# UPS-MAF-APU.net
KiCad netlist of a schematic drawn in EAGLE
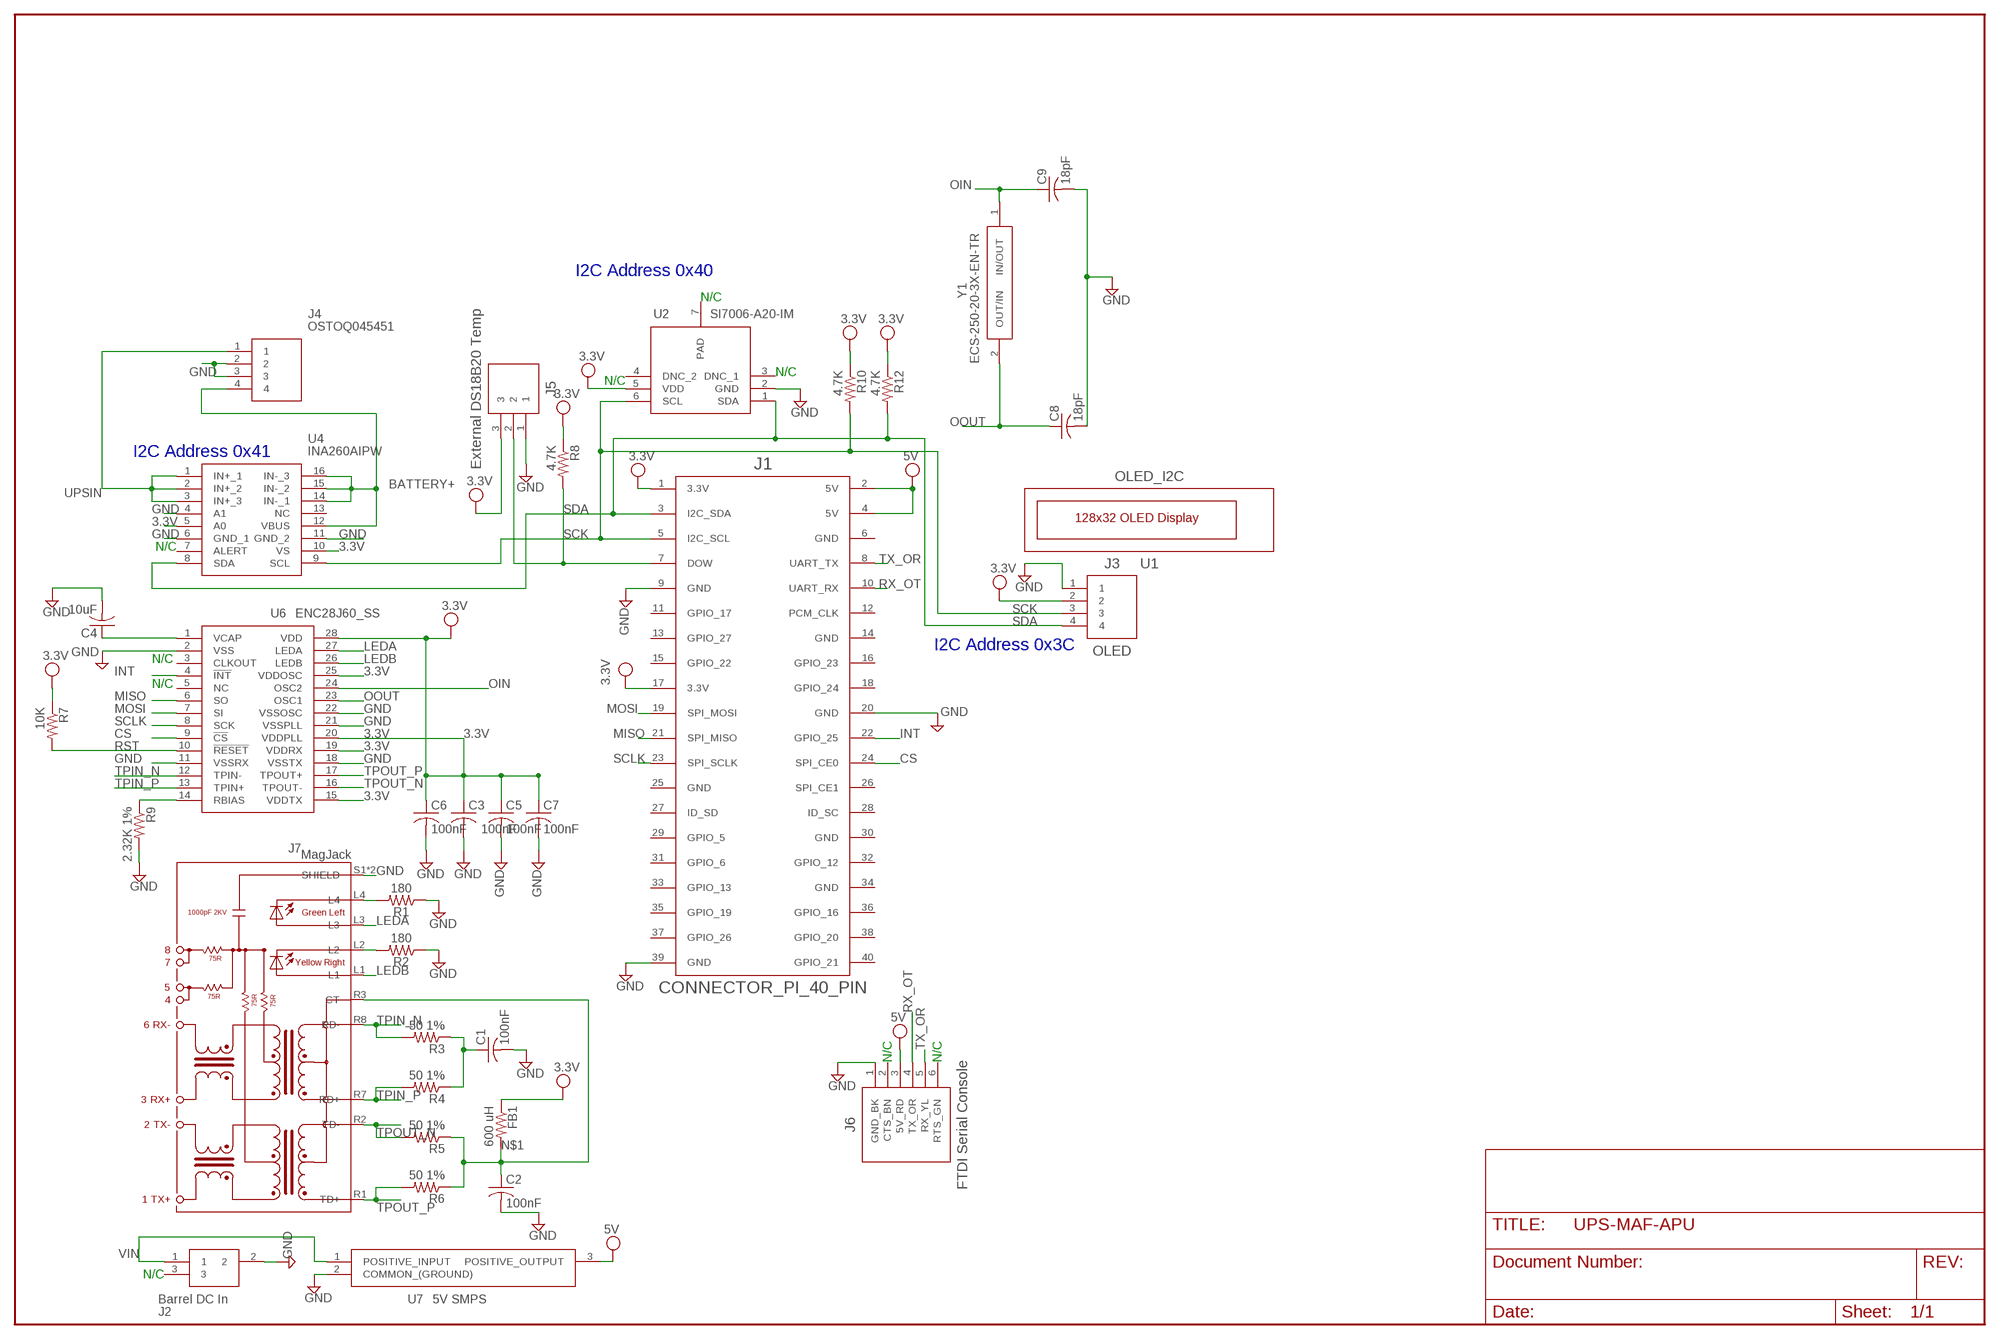
[diagram p0: schematic, sheet 1]

(export (version "E")
  (design (tool "Eeschema 10.0.6"))
  (components
    (comp (ref "C1")
      (value "100nF")
      (footprint "eagle-import:C0603")
      (libsource (lib "eagle-import") (part "C-USC0603"))
    )
    (comp (ref "C2")
      (value "100nF")
      (footprint "eagle-import:C0603")
      (libsource (lib "eagle-import") (part "C-USC0603"))
    )
    (comp (ref "C3")
      (value "100nF")
      (footprint "eagle-import:C0603")
      (libsource (lib "eagle-import") (part "C-USC0603"))
    )
    (comp (ref "C4")
      (value "10uF")
      (footprint "eagle-import:C0805")
      (libsource (lib "eagle-import") (part "C-USC0805"))
    )
    (comp (ref "C5")
      (value "100nF")
      (footprint "eagle-import:C0603")
      (libsource (lib "eagle-import") (part "C-USC0603"))
    )
    (comp (ref "C6")
      (value "100nF")
      (footprint "eagle-import:C0603")
      (libsource (lib "eagle-import") (part "C-USC0603"))
    )
    (comp (ref "C7")
      (value "100nF")
      (footprint "eagle-import:C0603")
      (libsource (lib "eagle-import") (part "C-USC0603"))
    )
    (comp (ref "C8")
      (value "18pF")
      (footprint "eagle-import:C0603")
      (libsource (lib "eagle-import") (part "C-USC0603"))
    )
    (comp (ref "C9")
      (value "18pF")
      (footprint "eagle-import:C0603")
      (libsource (lib "eagle-import") (part "C-USC0603"))
    )
    (comp (ref "FB1")
      (value "600 uH")
      (footprint "eagle-import:R0805")
      (libsource (lib "eagle-import") (part "R-US_R0805"))
    )
    (comp (ref "J1")
      (value "CONNECTOR_PI_40_PIN")
      (footprint "eagle-import:2X20")
      (libsource (lib "eagle-import") (part "CONNECTOR_PI_40_PIN"))
    )
    (comp (ref "J2")
      (value "Barrel DC In")
      (footprint "eagle-import:PJ-102AH")
      (fields
        (field (name "MANUFACTURER_PART_NUMBER") "PJ-102AH")
        (field (name "MOUSER_PART_NUMBER") "490-PJ-102AH")
      )
      (libsource (lib "eagle-import") (part "PJ-102AH"))
    )
    (comp (ref "J3")
      (value "OLED")
      (footprint "eagle-import:ESQ-104-XX-X-S")
      (libsource (lib "eagle-import") (part "CONNECTOR_4"))
    )
    (comp (ref "J4")
      (value "OSTOQ045451")
      (footprint "eagle-import:OSTOQ045451")
      (libsource (lib "eagle-import") (part "OSTOQ045451"))
    )
    (comp (ref "J5")
      (value "External DS18B20 Temp")
      (footprint "eagle-import:MOLEX_70553-0002")
      (libsource (lib "eagle-import") (part "CONNECTOR-3"))
    )
    (comp (ref "J6")
      (value "FTDI Serial Console")
      (footprint "eagle-import:ESQ-106-XX-X-S")
      (libsource (lib "eagle-import") (part "CONNECTOR-6-FTDI"))
    )
    (comp (ref "J7")
      (value "MagJack")
      (footprint "eagle-import:WIZNET_RB1-125BAG1A")
      (fields (field (name "MF") "WIZnet") (field (name "MP") "RB1-125BAG1A"))
      (libsource (lib "eagle-import") (part "RB1-125BAG1A"))
    )
    (comp (ref "R1")
      (value "180")
      (footprint "eagle-import:0603")
      (libsource (lib "eagle-import") (part "180OHM-0603-1/10W-1%"))
    )
    (comp (ref "R2")
      (value "180")
      (footprint "eagle-import:0603")
      (libsource (lib "eagle-import") (part "180OHM-0603-1/10W-1%"))
    )
    (comp (ref "R3")
      (value "50 1%")
      (footprint "eagle-import:R0805")
      (libsource (lib "eagle-import") (part "R-US_R0805"))
    )
    (comp (ref "R4")
      (value "50 1%")
      (footprint "eagle-import:R0805")
      (libsource (lib "eagle-import") (part "R-US_R0805"))
    )
    (comp (ref "R5")
      (value "50 1%")
      (footprint "eagle-import:R0805")
      (libsource (lib "eagle-import") (part "R-US_R0805"))
    )
    (comp (ref "R6")
      (value "50 1%")
      (footprint "eagle-import:R0805")
      (libsource (lib "eagle-import") (part "R-US_R0805"))
    )
    (comp (ref "R7")
      (value "10K")
      (footprint "eagle-import:R0805")
      (libsource (lib "eagle-import") (part "R-US_R0805"))
    )
    (comp (ref "R8")
      (value "4.7K")
      (footprint "eagle-import:R0805")
      (libsource (lib "eagle-import") (part "R-US_R0805"))
    )
    (comp (ref "R9")
      (value "2.32K 1%")
      (footprint "eagle-import:R0805")
      (libsource (lib "eagle-import") (part "R-US_R0805"))
    )
    (comp (ref "R10")
      (value "4.7K")
      (footprint "eagle-import:R0805")
      (libsource (lib "eagle-import") (part "R-US_R0805"))
    )
    (comp (ref "R12")
      (value "4.7K")
      (footprint "eagle-import:R0805")
      (libsource (lib "eagle-import") (part "R-US_R0805"))
    )
    (comp (ref "U1")
      (value "OLED_I2C")
      (footprint "eagle-import:OLED-I2C")
      (libsource (lib "eagle-import") (part "OLED_I2C"))
    )
    (comp (ref "U2")
      (value "SI7006-A20-IM")
      (footprint "eagle-import:SON100P300X300X80-7N")
      (fields
        (field (name "MANUFACTURER_PART_NUMBER") "Si7006-A20-IM")
        (field (name "MOUSER_PART_NUMBER") "634-SI7006-A20-IM")
        (field (name "RS_PART_NUMBER") "8652274P")
      )
      (libsource (lib "eagle-import") (part "SI7006-A20-IM"))
    )
    (comp (ref "U4")
      (value "INA260AIPW")
      (footprint "eagle-import:SOP65P640X120-16N")
      (fields (field (name "MOUSER_PART_NUMBER") "595-INA260AIPW"))
      (libsource (lib "eagle-import") (part "INA260AIPW"))
    )
    (comp (ref "U6")
      (value "ENC28J60_SS")
      (footprint "eagle-import:SOP65P780X200-28N")
      (fields
        (field (name "MANUFACTURER_PART_NUMBER") "ENC28J60/SS")
        (field (name "MOUSER_PART_NUMBER") "579-ENC28J60/SS")
        (field (name "RS_PART_NUMBER") "6665713P")
      )
      (libsource (lib "eagle-import") (part "ENC28J60_SS"))
    )
    (comp (ref "U7")
      (value "5V SMPS")
      (footprint "eagle-import:OKI-78SR-HORIZONTAL")
      (fields
        (field (name "MANUFACTURER_PART_NUMBER") "OKI-78SR-5/1.5-W36H-C")
        (field (name "MOUSER_PART_NUMBER") "580-OKI78SR51.5W36HC")
        (field (name "RS_PART_NUMBER") "1736931")
      )
      (libsource (lib "eagle-import") (part "OKI-78SR-5_1.5-W36H-C"))
    )
    (comp (ref "Y1")
      (value "ECS-250-20-3X-EN-TR")
      (footprint "eagle-import:ECS250203XENTR")
      (libsource (lib "eagle-import") (part "ECS-250-20-3X-EN-TR"))
    )
  )
  (nets
    (net (code "1") (name "/BATTERY+") (class "Default")
      (node (ref "J4") (pin "4") (pinfunction "4_4") (pintype "bidirectional"))
      (node (ref "U4") (pin "12") (pinfunction "VBUS_12") (pintype "power_in"))
      (node (ref "U4") (pin "14") (pinfunction "IN-_1_14") (pintype "bidirectional"))
      (node (ref "U4") (pin "15") (pinfunction "IN-_2_15") (pintype "bidirectional"))
      (node (ref "U4") (pin "16") (pinfunction "IN-_3_16") (pintype "bidirectional"))
    )
    (net (code "2") (name "/CS") (class "Default")
      (node (ref "J1") (pin "24") (pinfunction "SPI_CE0_24") (pintype "bidirectional"))
      (node (ref "U6") (pin "9") (pinfunction "~{CS}_9") (pintype "input"))
    )
    (net (code "3") (name "/INT") (class "Default")
      (node (ref "J1") (pin "22") (pinfunction "GPIO_25_22") (pintype "bidirectional"))
      (node (ref "U6") (pin "4") (pinfunction "~{INT}_4") (pintype "input"))
    )
    (net (code "4") (name "/LEDA") (class "Default")
      (node (ref "J7") (pin "L3") (pinfunction "L3_L3") (pintype "passive"))
      (node (ref "U6") (pin "27") (pinfunction "LEDA_27") (pintype "bidirectional"))
    )
    (net (code "5") (name "/LEDB") (class "Default")
      (node (ref "J7") (pin "L1") (pinfunction "L1_L1") (pintype "passive"))
      (node (ref "U6") (pin "26") (pinfunction "LEDB_26") (pintype "bidirectional"))
    )
    (net (code "6") (name "/MISO") (class "Default")
      (node (ref "J1") (pin "21") (pinfunction "SPI_MISO_21") (pintype "bidirectional"))
      (node (ref "U6") (pin "6") (pinfunction "SO_6") (pintype "bidirectional"))
    )
    (net (code "7") (name "/MOSI") (class "Default")
      (node (ref "J1") (pin "19") (pinfunction "SPI_MOSI_19") (pintype "bidirectional"))
      (node (ref "U6") (pin "7") (pinfunction "SI_7") (pintype "bidirectional"))
    )
    (net (code "8") (name "/N$1") (class "Default")
      (node (ref "C2") (pin "1") (pinfunction "1_1") (pintype "passive"))
      (node (ref "FB1") (pin "2") (pinfunction "2_2") (pintype "passive"))
      (node (ref "J7") (pin "R3") (pinfunction "CT_R3") (pintype "input"))
      (node (ref "R5") (pin "1") (pinfunction "1_1") (pintype "passive"))
      (node (ref "R6") (pin "1") (pinfunction "1_1") (pintype "passive"))
    )
    (net (code "9") (name "/OIN") (class "Default")
      (node (ref "C9") (pin "1") (pinfunction "1_1") (pintype "passive"))
      (node (ref "U6") (pin "24") (pinfunction "OSC2_24") (pintype "bidirectional"))
      (node (ref "Y1") (pin "1") (pinfunction "IN/OUT_1") (pintype "bidirectional"))
    )
    (net (code "10") (name "/OOUT") (class "Default")
      (node (ref "C8") (pin "1") (pinfunction "1_1") (pintype "passive"))
      (node (ref "U6") (pin "23") (pinfunction "OSC1_23") (pintype "bidirectional"))
      (node (ref "Y1") (pin "2") (pinfunction "OUT/IN_2") (pintype "bidirectional"))
    )
    (net (code "11") (name "/PAD") (class "Default")
      (node (ref "U2") (pin "7") (pinfunction "PAD_7") (pintype "power_in"))
    )
    (net (code "12") (name "/RST") (class "Default")
      (node (ref "R7") (pin "2") (pinfunction "2_2") (pintype "passive"))
      (node (ref "U6") (pin "10") (pinfunction "~{RESET}_10") (pintype "bidirectional"))
    )
    (net (code "13") (name "/RX_OT") (class "Default")
      (node (ref "J1") (pin "10") (pinfunction "UART_RX_10") (pintype "bidirectional"))
      (node (ref "J6") (pin "4") (pinfunction "TX_OR_4") (pintype "bidirectional"))
    )
    (net (code "14") (name "/SCK") (class "Default")
      (node (ref "J1") (pin "5") (pinfunction "I2C_SCL_5") (pintype "bidirectional"))
      (node (ref "J3") (pin "3") (pinfunction "3_3") (pintype "bidirectional"))
      (node (ref "R10") (pin "2") (pinfunction "2_2") (pintype "passive"))
      (node (ref "U2") (pin "6") (pinfunction "SCL_6") (pintype "input"))
      (node (ref "U4") (pin "9") (pinfunction "SCL_9") (pintype "bidirectional"))
    )
    (net (code "15") (name "/SCLK") (class "Default")
      (node (ref "J1") (pin "23") (pinfunction "SPI_SCLK_23") (pintype "bidirectional"))
      (node (ref "U6") (pin "8") (pinfunction "SCK_8") (pintype "bidirectional"))
    )
    (net (code "16") (name "/SDA") (class "Default")
      (node (ref "J1") (pin "3") (pinfunction "I2C_SDA_3") (pintype "bidirectional"))
      (node (ref "J3") (pin "4") (pinfunction "4_4") (pintype "bidirectional"))
      (node (ref "R12") (pin "2") (pinfunction "2_2") (pintype "passive"))
      (node (ref "U2") (pin "1") (pinfunction "SDA_1") (pintype "bidirectional"))
      (node (ref "U4") (pin "8") (pinfunction "SDA_8") (pintype "bidirectional"))
    )
    (net (code "17") (name "/TPIN_N") (class "Default")
      (node (ref "J7") (pin "R8") (pinfunction "RD-_R8") (pintype "input"))
      (node (ref "R3") (pin "2") (pinfunction "2_2") (pintype "passive"))
      (node (ref "U6") (pin "12") (pinfunction "TPIN-_12") (pintype "input"))
    )
    (net (code "18") (name "/TPIN_P") (class "Default")
      (node (ref "J7") (pin "R7") (pinfunction "RD+_R7") (pintype "input"))
      (node (ref "R4") (pin "2") (pinfunction "2_2") (pintype "passive"))
      (node (ref "U6") (pin "13") (pinfunction "TPIN+_13") (pintype "input"))
    )
    (net (code "19") (name "/TPOUT_N") (class "Default")
      (node (ref "J7") (pin "R2") (pinfunction "TD-_R2") (pintype "input"))
      (node (ref "R5") (pin "2") (pinfunction "2_2") (pintype "passive"))
      (node (ref "U6") (pin "16") (pinfunction "TPOUT-_16") (pintype "output"))
    )
    (net (code "20") (name "/TPOUT_P") (class "Default")
      (node (ref "J7") (pin "R1") (pinfunction "TD+_R1") (pintype "input"))
      (node (ref "R6") (pin "2") (pinfunction "2_2") (pintype "passive"))
      (node (ref "U6") (pin "17") (pinfunction "TPOUT+_17") (pintype "output"))
    )
    (net (code "21") (name "/TX_OR") (class "Default")
      (node (ref "J1") (pin "8") (pinfunction "UART_TX_8") (pintype "bidirectional"))
      (node (ref "J6") (pin "5") (pinfunction "RX_YL_5") (pintype "bidirectional"))
    )
    (net (code "22") (name "/UPSIN") (class "Default")
      (node (ref "J4") (pin "1") (pinfunction "1_1") (pintype "bidirectional"))
      (node (ref "U4") (pin "1") (pinfunction "IN+_1_1") (pintype "bidirectional"))
      (node (ref "U4") (pin "2") (pinfunction "IN+_2_2") (pintype "bidirectional"))
      (node (ref "U4") (pin "3") (pinfunction "IN+_3_3") (pintype "bidirectional"))
    )
    (net (code "23") (name "/VIN") (class "Default")
      (node (ref "J2") (pin "1") (pinfunction "1_1") (pintype "bidirectional"))
      (node (ref "U7") (pin "1") (pinfunction "POSITIVE_INPUT_1") (pintype "input"))
    )
    (net (code "24") (name "3.3V") (class "Default")
      (node (ref "C3") (pin "1") (pinfunction "1_1") (pintype "passive"))
      (node (ref "C5") (pin "1") (pinfunction "1_1") (pintype "passive"))
      (node (ref "C6") (pin "1") (pinfunction "1_1") (pintype "passive"))
      (node (ref "C7") (pin "1") (pinfunction "1_1") (pintype "passive"))
      (node (ref "FB1") (pin "1") (pinfunction "1_1") (pintype "passive"))
      (node (ref "J1") (pin "1") (pinfunction "3.3V_1") (pintype "bidirectional"))
      (node (ref "J1") (pin "17") (pinfunction "3.3V_17") (pintype "bidirectional"))
      (node (ref "J3") (pin "2") (pinfunction "2_2") (pintype "bidirectional"))
      (node (ref "J5") (pin "3") (pinfunction "3_3") (pintype "bidirectional"))
      (node (ref "R10") (pin "1") (pinfunction "1_1") (pintype "passive"))
      (node (ref "R12") (pin "1") (pinfunction "1_1") (pintype "passive"))
      (node (ref "R7") (pin "1") (pinfunction "1_1") (pintype "passive"))
      (node (ref "R8") (pin "1") (pinfunction "1_1") (pintype "passive"))
      (node (ref "U2") (pin "5") (pinfunction "VDD_5") (pintype "power_in"))
      (node (ref "U4") (pin "10") (pinfunction "VS_10") (pintype "power_in"))
      (node (ref "U4") (pin "5") (pinfunction "A0_5") (pintype "input"))
      (node (ref "U6") (pin "15") (pinfunction "VDDTX_15") (pintype "power_in"))
      (node (ref "U6") (pin "19") (pinfunction "VDDRX_19") (pintype "power_in"))
      (node (ref "U6") (pin "20") (pinfunction "VDDPLL_20") (pintype "power_in"))
      (node (ref "U6") (pin "25") (pinfunction "VDDOSC_25") (pintype "power_in"))
      (node (ref "U6") (pin "28") (pinfunction "VDD_28") (pintype "power_in"))
    )
    (net (code "25") (name "5V") (class "Default")
      (node (ref "J1") (pin "2") (pinfunction "5V_2") (pintype "bidirectional"))
      (node (ref "J1") (pin "4") (pinfunction "5V_4") (pintype "bidirectional"))
      (node (ref "J6") (pin "3") (pinfunction "5V_RD_3") (pintype "bidirectional"))
      (node (ref "U7") (pin "3") (pinfunction "POSITIVE_OUTPUT_3") (pintype "output"))
    )
    (net (code "26") (name "GND") (class "Default")
      (node (ref "C1") (pin "2") (pinfunction "2_2") (pintype "passive"))
      (node (ref "C2") (pin "2") (pinfunction "2_2") (pintype "passive"))
      (node (ref "C3") (pin "2") (pinfunction "2_2") (pintype "passive"))
      (node (ref "C4") (pin "2") (pinfunction "2_2") (pintype "passive"))
      (node (ref "C5") (pin "2") (pinfunction "2_2") (pintype "passive"))
      (node (ref "C6") (pin "2") (pinfunction "2_2") (pintype "passive"))
      (node (ref "C7") (pin "2") (pinfunction "2_2") (pintype "passive"))
      (node (ref "C8") (pin "2") (pinfunction "2_2") (pintype "passive"))
      (node (ref "C9") (pin "2") (pinfunction "2_2") (pintype "passive"))
      (node (ref "J1") (pin "20") (pinfunction "GND_20") (pintype "bidirectional"))
      (node (ref "J1") (pin "39") (pinfunction "GND_39") (pintype "bidirectional"))
      (node (ref "J1") (pin "9") (pinfunction "GND_9") (pintype "bidirectional"))
      (node (ref "J2") (pin "2") (pinfunction "2_2") (pintype "bidirectional"))
      (node (ref "J3") (pin "1") (pinfunction "1_1") (pintype "bidirectional"))
      (node (ref "J4") (pin "2") (pinfunction "2_2") (pintype "bidirectional"))
      (node (ref "J4") (pin "3") (pinfunction "3_3") (pintype "bidirectional"))
      (node (ref "J5") (pin "1") (pinfunction "1_1") (pintype "bidirectional"))
      (node (ref "J6") (pin "1") (pinfunction "GND_BK_1") (pintype "bidirectional"))
      (node (ref "J7") (pin "S1") (pinfunction "SHIELD_S1") (pintype "input"))
      (node (ref "J7") (pin "S2") (pinfunction "SHIELD_S2") (pintype "input"))
      (node (ref "R1") (pin "1") (pinfunction "1_1") (pintype "passive"))
      (node (ref "R2") (pin "1") (pinfunction "1_1") (pintype "passive"))
      (node (ref "R9") (pin "2") (pinfunction "2_2") (pintype "passive"))
      (node (ref "U2") (pin "2") (pinfunction "GND_2") (pintype "power_in"))
      (node (ref "U4") (pin "11") (pinfunction "GND_2_11") (pintype "power_in"))
      (node (ref "U4") (pin "4") (pinfunction "A1_4") (pintype "input"))
      (node (ref "U4") (pin "6") (pinfunction "GND_1_6") (pintype "power_in"))
      (node (ref "U6") (pin "11") (pinfunction "VSSRX_11") (pintype "power_in"))
      (node (ref "U6") (pin "18") (pinfunction "VSSTX_18") (pintype "power_in"))
      (node (ref "U6") (pin "2") (pinfunction "VSS_2") (pintype "power_in"))
      (node (ref "U6") (pin "21") (pinfunction "VSSPLL_21") (pintype "power_in"))
      (node (ref "U6") (pin "22") (pinfunction "VSSOSC_22") (pintype "power_in"))
      (node (ref "U7") (pin "2") (pinfunction "COMMON_(GROUND)_2") (pintype "bidirectional"))
    )
    (net (code "27") (name "Net-(C1-Pad1)") (class "Default")
      (node (ref "C1") (pin "1") (pinfunction "1_1") (pintype "passive"))
      (node (ref "R3") (pin "1") (pinfunction "1_1") (pintype "passive"))
      (node (ref "R4") (pin "1") (pinfunction "1_1") (pintype "passive"))
    )
    (net (code "28") (name "Net-(J1-DOW)") (class "Default")
      (node (ref "J1") (pin "7") (pinfunction "DOW_7") (pintype "bidirectional"))
      (node (ref "J5") (pin "2") (pinfunction "2_2") (pintype "bidirectional"))
      (node (ref "R8") (pin "2") (pinfunction "2_2") (pintype "passive"))
    )
    (net (code "29") (name "Net-(J7-PadL2)") (class "Default")
      (node (ref "J7") (pin "L2") (pinfunction "L2_L2") (pintype "passive"))
      (node (ref "R2") (pin "2") (pinfunction "2_2") (pintype "passive"))
    )
    (net (code "30") (name "Net-(J7-PadL4)") (class "Default")
      (node (ref "J7") (pin "L4") (pinfunction "L4_L4") (pintype "passive"))
      (node (ref "R1") (pin "2") (pinfunction "2_2") (pintype "passive"))
    )
    (net (code "31") (name "Net-(U6-RBIAS)") (class "Default")
      (node (ref "R9") (pin "1") (pinfunction "1_1") (pintype "passive"))
      (node (ref "U6") (pin "14") (pinfunction "RBIAS_14") (pintype "bidirectional"))
    )
    (net (code "32") (name "Net-(U6-VCAP)") (class "Default")
      (node (ref "C4") (pin "1") (pinfunction "1_1") (pintype "passive"))
      (node (ref "U6") (pin "1") (pinfunction "VCAP_1") (pintype "bidirectional"))
    )
    (net (code "33") (name "unconnected-(J1-GND-Pad6)") (class "Default")
      (node (ref "J1") (pin "6") (pinfunction "GND_6") (pintype "bidirectional"))
    )
    (net (code "34") (name "unconnected-(J1-GND-Pad14)") (class "Default")
      (node (ref "J1") (pin "14") (pinfunction "GND_14") (pintype "bidirectional"))
    )
    (net (code "35") (name "unconnected-(J1-GND-Pad25)") (class "Default")
      (node (ref "J1") (pin "25") (pinfunction "GND_25") (pintype "bidirectional"))
    )
    (net (code "36") (name "unconnected-(J1-GND-Pad30)") (class "Default")
      (node (ref "J1") (pin "30") (pinfunction "GND_30") (pintype "bidirectional"))
    )
    (net (code "37") (name "unconnected-(J1-GND-Pad34)") (class "Default")
      (node (ref "J1") (pin "34") (pinfunction "GND_34") (pintype "bidirectional"))
    )
    (net (code "38") (name "unconnected-(J1-GPIO_5-Pad29)") (class "Default")
      (node (ref "J1") (pin "29") (pinfunction "GPIO_5_29") (pintype "bidirectional"))
    )
    (net (code "39") (name "unconnected-(J1-GPIO_6-Pad31)") (class "Default")
      (node (ref "J1") (pin "31") (pinfunction "GPIO_6_31") (pintype "bidirectional"))
    )
    (net (code "40") (name "unconnected-(J1-GPIO_12-Pad32)") (class "Default")
      (node (ref "J1") (pin "32") (pinfunction "GPIO_12_32") (pintype "bidirectional"))
    )
    (net (code "41") (name "unconnected-(J1-GPIO_13-Pad33)") (class "Default")
      (node (ref "J1") (pin "33") (pinfunction "GPIO_13_33") (pintype "bidirectional"))
    )
    (net (code "42") (name "unconnected-(J1-GPIO_16-Pad36)") (class "Default")
      (node (ref "J1") (pin "36") (pinfunction "GPIO_16_36") (pintype "bidirectional"))
    )
    (net (code "43") (name "unconnected-(J1-GPIO_17-Pad11)") (class "Default")
      (node (ref "J1") (pin "11") (pinfunction "GPIO_17_11") (pintype "bidirectional"))
    )
    (net (code "44") (name "unconnected-(J1-GPIO_19-Pad35)") (class "Default")
      (node (ref "J1") (pin "35") (pinfunction "GPIO_19_35") (pintype "bidirectional"))
    )
    (net (code "45") (name "unconnected-(J1-GPIO_20-Pad38)") (class "Default")
      (node (ref "J1") (pin "38") (pinfunction "GPIO_20_38") (pintype "bidirectional"))
    )
    (net (code "46") (name "unconnected-(J1-GPIO_21-Pad40)") (class "Default")
      (node (ref "J1") (pin "40") (pinfunction "GPIO_21_40") (pintype "bidirectional"))
    )
    (net (code "47") (name "unconnected-(J1-GPIO_22-Pad15)") (class "Default")
      (node (ref "J1") (pin "15") (pinfunction "GPIO_22_15") (pintype "bidirectional"))
    )
    (net (code "48") (name "unconnected-(J1-GPIO_23-Pad16)") (class "Default")
      (node (ref "J1") (pin "16") (pinfunction "GPIO_23_16") (pintype "bidirectional"))
    )
    (net (code "49") (name "unconnected-(J1-GPIO_24-Pad18)") (class "Default")
      (node (ref "J1") (pin "18") (pinfunction "GPIO_24_18") (pintype "bidirectional"))
    )
    (net (code "50") (name "unconnected-(J1-GPIO_26-Pad37)") (class "Default")
      (node (ref "J1") (pin "37") (pinfunction "GPIO_26_37") (pintype "bidirectional"))
    )
    (net (code "51") (name "unconnected-(J1-GPIO_27-Pad13)") (class "Default")
      (node (ref "J1") (pin "13") (pinfunction "GPIO_27_13") (pintype "bidirectional"))
    )
    (net (code "52") (name "unconnected-(J1-ID_SC-Pad28)") (class "Default")
      (node (ref "J1") (pin "28") (pinfunction "ID_SC_28") (pintype "bidirectional"))
    )
    (net (code "53") (name "unconnected-(J1-ID_SD-Pad27)") (class "Default")
      (node (ref "J1") (pin "27") (pinfunction "ID_SD_27") (pintype "bidirectional"))
    )
    (net (code "54") (name "unconnected-(J1-PCM_CLK-Pad12)") (class "Default")
      (node (ref "J1") (pin "12") (pinfunction "PCM_CLK_12") (pintype "bidirectional"))
    )
    (net (code "55") (name "unconnected-(J1-SPI_CE1-Pad26)") (class "Default")
      (node (ref "J1") (pin "26") (pinfunction "SPI_CE1_26") (pintype "bidirectional"))
    )
    (net (code "56") (name "unconnected-(J2-Pad3)") (class "Default")
      (node (ref "J2") (pin "3") (pinfunction "3_3") (pintype "bidirectional"))
    )
    (net (code "57") (name "unconnected-(J6-CTS_BN-Pad2)") (class "Default")
      (node (ref "J6") (pin "2") (pinfunction "CTS_BN_2") (pintype "bidirectional"))
    )
    (net (code "58") (name "unconnected-(J6-RTS_GN-Pad6)") (class "Default")
      (node (ref "J6") (pin "6") (pinfunction "RTS_GN_6") (pintype "bidirectional"))
    )
    (net (code "59") (name "unconnected-(U2-DNC_1-Pad3)") (class "Default")
      (node (ref "U2") (pin "3") (pinfunction "DNC_1_3") (pintype "bidirectional"))
    )
    (net (code "60") (name "unconnected-(U2-DNC_2-Pad4)") (class "Default")
      (node (ref "U2") (pin "4") (pinfunction "DNC_2_4") (pintype "bidirectional"))
    )
    (net (code "61") (name "unconnected-(U4-ALERT-Pad7)") (class "Default")
      (node (ref "U4") (pin "7") (pinfunction "ALERT_7") (pintype "output"))
    )
    (net (code "62") (name "unconnected-(U4-NC-Pad13)") (class "Default")
      (node (ref "U4") (pin "13") (pinfunction "NC_13") (pintype "no_connect"))
    )
    (net (code "63") (name "unconnected-(U6-CLKOUT-Pad3)") (class "Default")
      (node (ref "U6") (pin "3") (pinfunction "CLKOUT_3") (pintype "output"))
    )
    (net (code "64") (name "unconnected-(U6-NC-Pad5)") (class "Default")
      (node (ref "U6") (pin "5") (pinfunction "NC_5") (pintype "no_connect"))
    )
  )
)
